# Teensylu-1_2.net
KiCad netlist of a schematic drawn in EAGLE
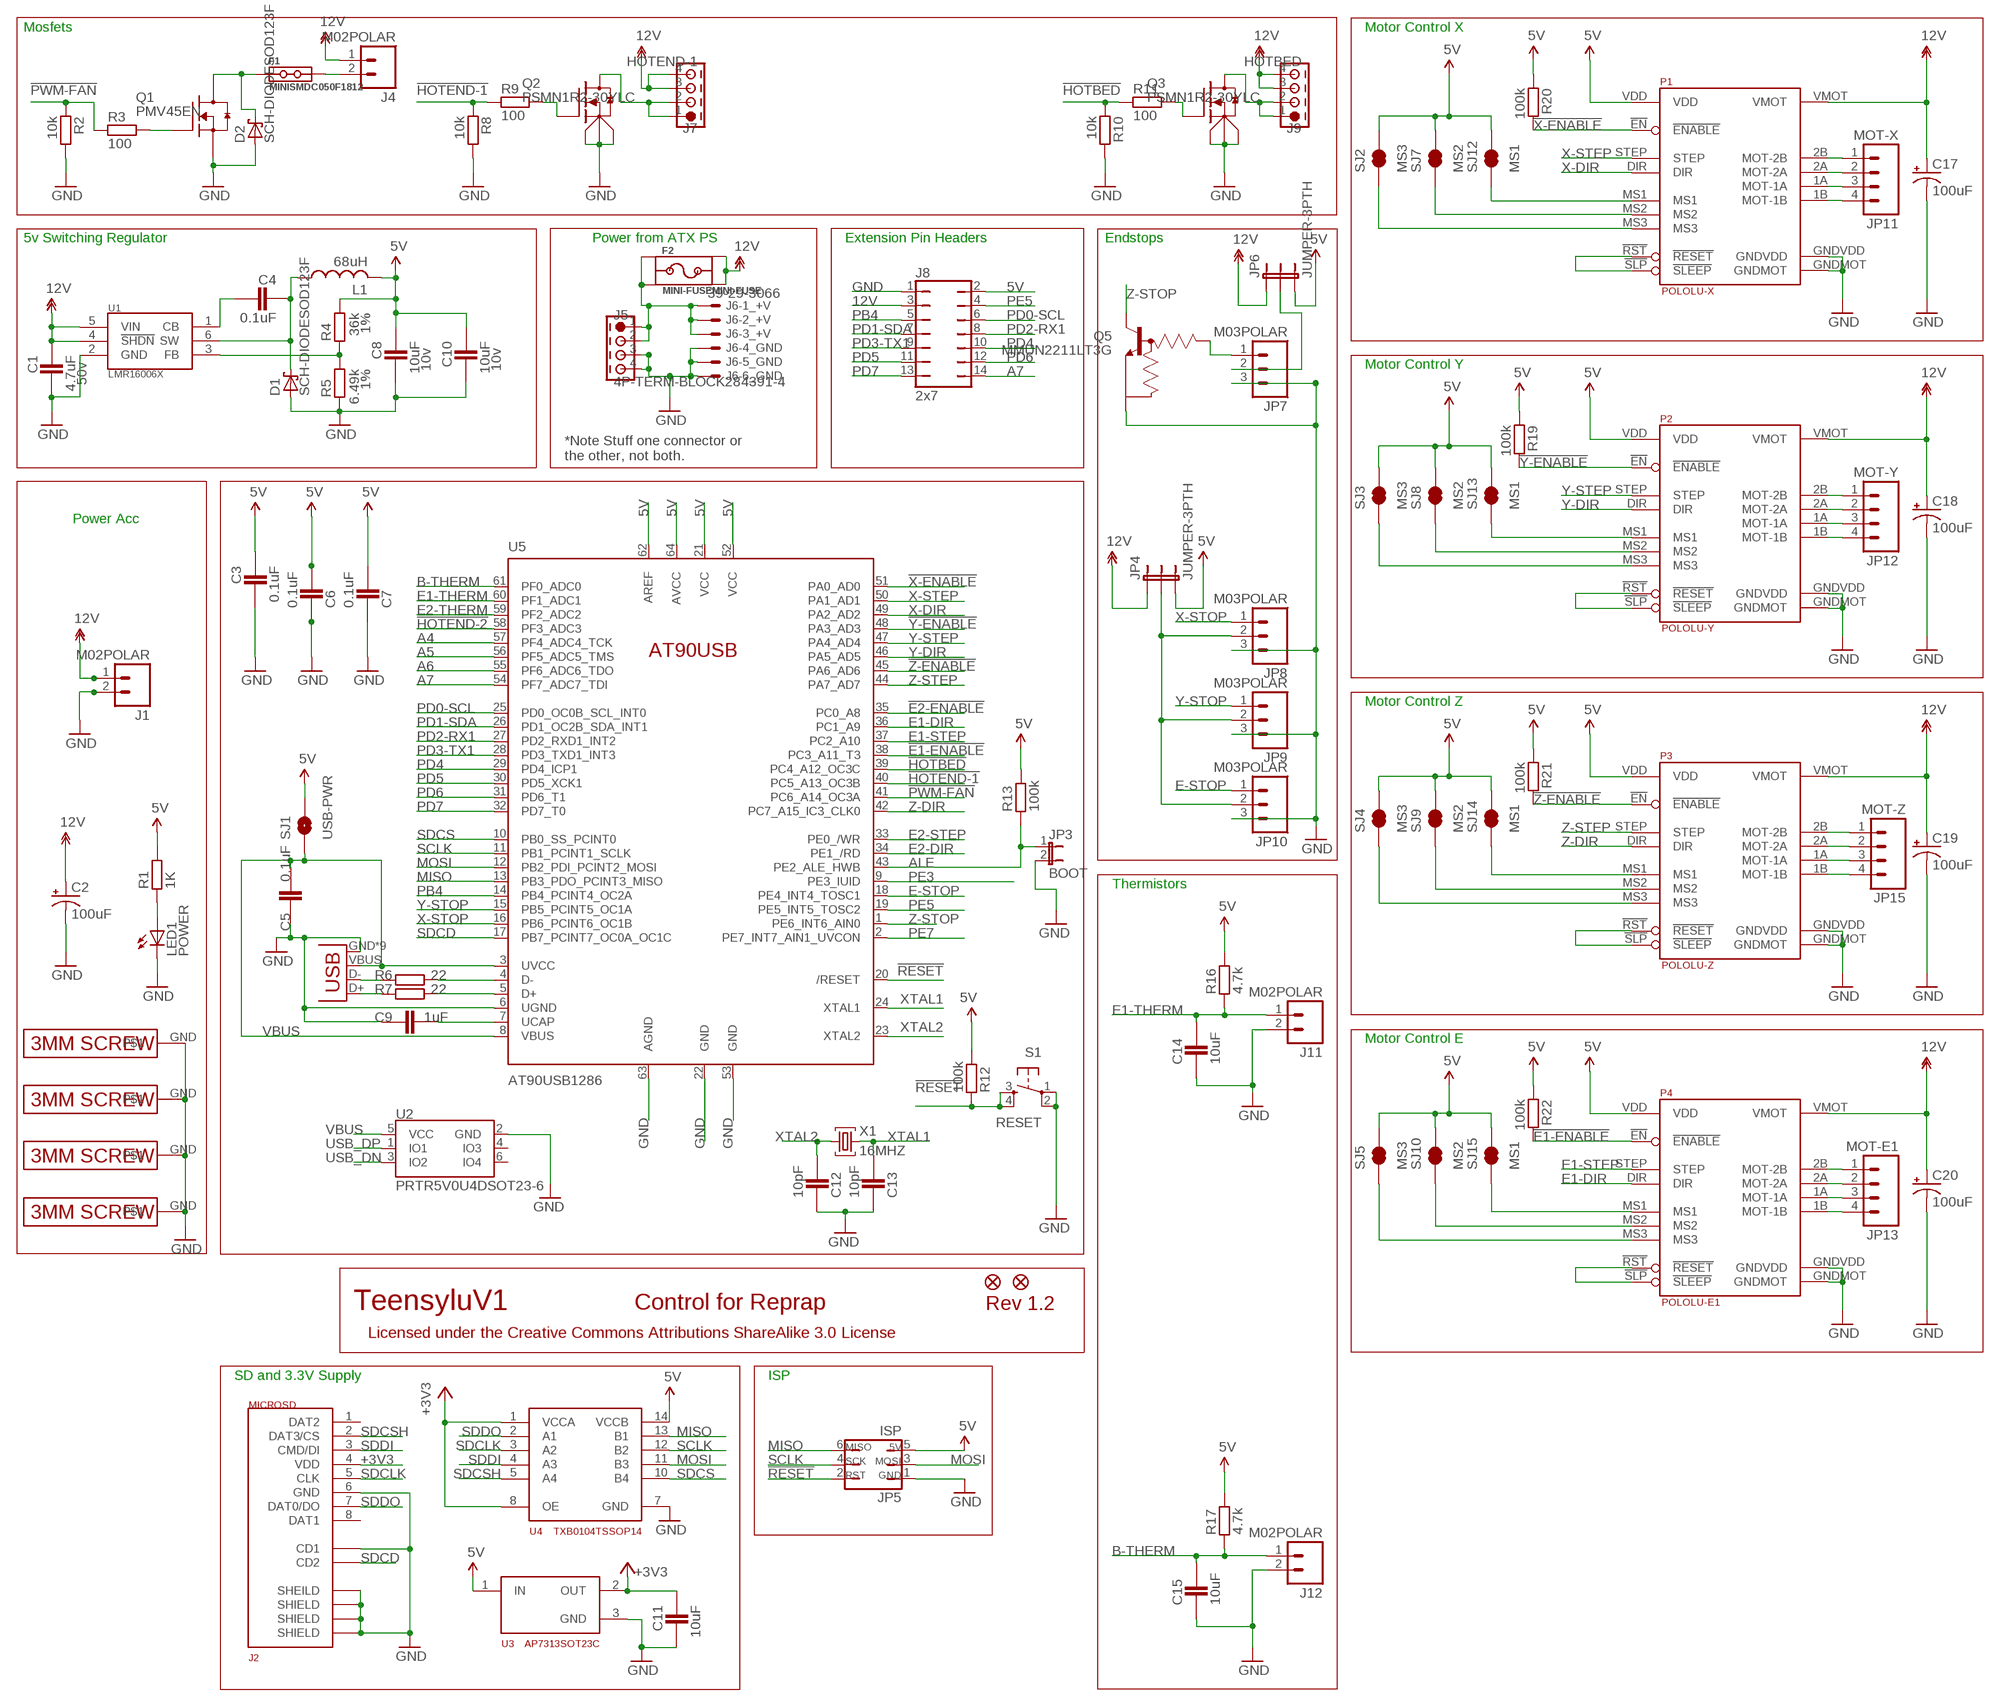
[diagram p0: schematic, sheet 1]

(export (version "E")
  (design (tool "Eeschema 10.0.6"))
  (components
    (comp (ref "C1")
      (value "4.7uF")
      (footprint "eagle-import:CAPC3215X168N")
      (fields
        (field (name "MANUFACTURER") "Yaiyo Yuden")
        (field (name "MANUFACTURER_PART_NUMBER") "UMK316AB7475KL-T")
        (field (name "TOLERANCE") "10%")
        (field (name "VDC") "50v")
      )
      (libsource (lib "eagle-import") (part "CAPACITOR_1206"))
    )
    (comp (ref "C2")
      (value "100uF")
      (footprint "eagle-import:PANASONIC_D")
      (fields
        (field (name "MANUFACTURER") "Panasonic")
        (field (name "MANUFACTURER_PART_NUMBER") "EEE-FTH101XAP")
        (field (name "TOLERANCE") "20%")
      )
      (libsource (lib "eagle-import") (part "CPOL-USD"))
    )
    (comp (ref "C3")
      (value "0.1uF")
      (footprint "eagle-import:CAPC1608X92N")
      (fields
        (field (name "MANUFACTURER") "Murata")
        (field (name "MANUFACTURER_PART_NUMBER") "GRM188R71C104KA01D")
        (field (name "TOLERANCE") "10%")
      )
      (libsource (lib "eagle-import") (part "CAPACITOR_0603"))
    )
    (comp (ref "C4")
      (value "0.1uF")
      (footprint "eagle-import:CAPC1608X92N")
      (fields
        (field (name "MANUFACTURER") "Samsung")
        (field (name "MANUFACTURER_PART_NUMBER") "CL10B104KB8NNNC")
        (field (name "TOLERANCE") "10%")
      )
      (libsource (lib "eagle-import") (part "CAPACITOR_0603"))
    )
    (comp (ref "C5")
      (value "0.1uF")
      (footprint "eagle-import:CAPC1608X92N")
      (fields
        (field (name "MANUFACTURER") "Murata")
        (field (name "MANUFACTURER_PART_NUMBER") "GRM188R71C104KA01D")
        (field (name "TOLERANCE") "10%")
      )
      (libsource (lib "eagle-import") (part "CAPACITOR_0603"))
    )
    (comp (ref "C6")
      (value "0.1uF")
      (footprint "eagle-import:CAPC1608X92N")
      (fields
        (field (name "MANUFACTURER") "Murata")
        (field (name "MANUFACTURER_PART_NUMBER") "GRM188R71C104KA01D")
        (field (name "TOLERANCE") "10%")
      )
      (libsource (lib "eagle-import") (part "CAPACITOR_0603"))
    )
    (comp (ref "C7")
      (value "0.1uF")
      (footprint "eagle-import:CAPC1608X92N")
      (fields
        (field (name "MANUFACTURER") "Murata")
        (field (name "MANUFACTURER_PART_NUMBER") "GRM188R71C104KA01D")
        (field (name "TOLERANCE") "10%")
      )
      (libsource (lib "eagle-import") (part "CAPACITOR_0603"))
    )
    (comp (ref "C8")
      (value "10uF")
      (footprint "eagle-import:CAPC2012X145AN")
      (fields
        (field (name "MANUFACTURER") "Murata")
        (field (name "MANUFACTURER_PART_NUMBER") "GRM21BR71A106KE51L")
        (field (name "TOLERANCE") "10%")
        (field (name "VDC") "10v")
      )
      (libsource (lib "eagle-import") (part "CAPACITOR_0805"))
    )
    (comp (ref "C9")
      (value "1uF")
      (footprint "eagle-import:CAPC1608X92N")
      (fields
        (field (name "MANUFACTURER") "Samsung")
        (field (name "MANUFACTURER_PART_NUMBER") "CL10A105MO8NNNC")
        (field (name "TOLERANCE") "20%")
      )
      (libsource (lib "eagle-import") (part "CAPACITOR_0603"))
    )
    (comp (ref "C10")
      (value "10uF")
      (footprint "eagle-import:CAPC2012X145AN")
      (fields
        (field (name "MANUFACTURER") "Murata")
        (field (name "MANUFACTURER_PART_NUMBER") "GRM21BR71A106KE51L")
        (field (name "TOLERANCE") "10%")
        (field (name "VDC") "10v")
      )
      (libsource (lib "eagle-import") (part "CAPACITOR_0805"))
    )
    (comp (ref "C11")
      (value "10uF")
      (footprint "eagle-import:CAPC1608X92N")
      (fields
        (field (name "MANUFACTURER") "Murata")
        (field (name "MANUFACTURER_PART_NUMBER") "GRM188R61C106MA73D")
        (field (name "TOLERANCE") "20%")
      )
      (libsource (lib "eagle-import") (part "CAPACITOR_0603"))
    )
    (comp (ref "C12")
      (value "10pF")
      (footprint "eagle-import:CAPC1608X92N")
      (fields
        (field (name "MANUFACTURER") "Samsung")
        (field (name "MANUFACTURER_PART_NUMBER") "CL10C100JB8NCNC")
        (field (name "TOLERANCE") "5%")
      )
      (libsource (lib "eagle-import") (part "CAPACITOR_0603"))
    )
    (comp (ref "C13")
      (value "10pF")
      (footprint "eagle-import:CAPC1608X92N")
      (fields
        (field (name "MANUFACTURER") "Samsung")
        (field (name "MANUFACTURER_PART_NUMBER") "CL10C100JB8NCNC")
        (field (name "TOLERANCE") "5%")
      )
      (libsource (lib "eagle-import") (part "CAPACITOR_0603"))
    )
    (comp (ref "C14")
      (value "10uF")
      (footprint "eagle-import:CAPC1608X92N")
      (fields
        (field (name "MANUFACTURER") "Murata")
        (field (name "MANUFACTURER_PART_NUMBER") "GRM188R61C106MA73D")
        (field (name "TOLERANCE") "20%")
      )
      (libsource (lib "eagle-import") (part "CAPACITOR_0603"))
    )
    (comp (ref "C15")
      (value "10uF")
      (footprint "eagle-import:CAPC1608X92N")
      (fields
        (field (name "MANUFACTURER") "Murata")
        (field (name "MANUFACTURER_PART_NUMBER") "GRM188R61C106MA73D")
        (field (name "TOLERANCE") "20%")
      )
      (libsource (lib "eagle-import") (part "CAPACITOR_0603"))
    )
    (comp (ref "C17")
      (value "100uF")
      (footprint "eagle-import:PANASONIC_D")
      (fields
        (field (name "MANUFACTURER") "Panasonic")
        (field (name "MANUFACTURER_PART_NUMBER") "EEE-FTH101XAP")
        (field (name "TOLERANCE") "20%")
      )
      (libsource (lib "eagle-import") (part "CPOL-USD"))
    )
    (comp (ref "C18")
      (value "100uF")
      (footprint "eagle-import:PANASONIC_D")
      (fields
        (field (name "MANUFACTURER") "Panasonic")
        (field (name "MANUFACTURER_PART_NUMBER") "EEE-FTH101XAP")
        (field (name "TOLERANCE") "20%")
      )
      (libsource (lib "eagle-import") (part "CPOL-USD"))
    )
    (comp (ref "C19")
      (value "100uF")
      (footprint "eagle-import:PANASONIC_D")
      (fields
        (field (name "MANUFACTURER") "Panasonic")
        (field (name "MANUFACTURER_PART_NUMBER") "EEE-FTH101XAP")
        (field (name "TOLERANCE") "20%")
      )
      (libsource (lib "eagle-import") (part "CPOL-USD"))
    )
    (comp (ref "C20")
      (value "100uF")
      (footprint "eagle-import:PANASONIC_D")
      (fields
        (field (name "MANUFACTURER") "Panasonic")
        (field (name "MANUFACTURER_PART_NUMBER") "EEE-FTH101XAP")
        (field (name "TOLERANCE") "20%")
      )
      (libsource (lib "eagle-import") (part "CPOL-USD"))
    )
    (comp (ref "D1")
      (value "SCH-DIODESOD123F")
      (footprint "eagle-import:SOD123F")
      (fields
        (field (name "MANUFACTURER") "NXP Semiconductors")
        (field (name "MANUFACTURER_PART_NUMBER") "PMEG4010CEH,115")
        (field (name "CURRENT") "1A")
        (field (name "MANUFACTURER_1") "NXP Semiconductors")
        (field (name "MANUFACTURER_PART_NUMBER_1") "PMEG4010CEH,115")
        (field (name "REVERSE_VOLTAGE") "40V")
      )
      (libsource (lib "eagle-import") (part "SCH-DIODESOD123F"))
    )
    (comp (ref "D2")
      (value "SCH-DIODESOD123F")
      (footprint "eagle-import:SOD123F")
      (fields
        (field (name "MANUFACTURER") "NXP Semiconductors")
        (field (name "MANUFACTURER_PART_NUMBER") "PMEG4010CEH,115")
        (field (name "CURRENT") "1A")
        (field (name "MANUFACTURER_1") "NXP Semiconductors")
      )
      (libsource (lib "eagle-import") (part "SCH-DIODESOD123F"))
    )
    (comp (ref "F1")
      (value "MINISMDC050F1812")
      (footprint "eagle-import:MINISMDC")
      (fields
        (field (name "MANUFACTURER") "TE Connectivity")
        (field (name "MANUFACTURER_PART_NUMBER") "MINISMDC050F-2")
      )
      (libsource (lib "eagle-import") (part "MINISMDC050F1812"))
    )
    (comp (ref "F2")
      (value "MINI-FUSEMINI-FUSE")
      (footprint "eagle-import:MINI_FUSE")
      (fields (field (name "MANUFACTURER") "Keystone") (field (name "MANUFACTURER_PART_NUMBER") "3568"))
      (libsource (lib "eagle-import") (part "MINI-FUSEMINI-FUSE"))
    )
    (comp (ref "J1")
      (value "M02POLAR")
      (footprint "eagle-import:MOLEX-1X2")
      (description "CONN HEADER 2POS .100 VERT TIN")
      (fields (field (name "MANUFACTURER") "Molex") (field (name "MANUFACTURER_PART_NUMBER") "0022272021"))
      (libsource (lib "eagle-import") (part "M02POLAR"))
    )
    (comp (ref "J2")
      (value "MICROSD")
      (footprint "eagle-import:AMPHENOL-MICROSD")
      (description "CONN MICRO SD CARD PUSH-PULL R/A")
      (fields
        (field (name "MANUFACTURER") "Amphenol")
        (field (name "MANUFACTURER_PART_NUMBER") "114-00841-68")
      )
      (libsource (lib "eagle-import") (part "MICROSD"))
    )
    (comp (ref "J3")
      (value "USB-MICRO-PTH")
      (footprint "eagle-import:USB-MICROB-PTH")
      (fields (field (name "MANUFACTURER") "FCI") (field (name "MANUFACTURER_PART_NUMBER") "10118194-0001LF"))
      (libsource (lib "eagle-import") (part "USB-MICRO-PTH"))
    )
    (comp (ref "J4")
      (value "M02POLAR")
      (footprint "eagle-import:MOLEX-1X2")
      (description "CONN HEADER 2POS .100 VERT TIN")
      (fields (field (name "MANUFACTURER") "Molex") (field (name "MANUFACTURER_PART_NUMBER") "0022272021"))
      (libsource (lib "eagle-import") (part "M02POLAR"))
    )
    (comp (ref "J5")
      (value "4P-TERM-BLOCK284391-4")
      (footprint "eagle-import:284391-4")
      (fields
        (field (name "MANUFACTURER") "TE Connectivity")
        (field (name "MANUFACTURER_PART_NUMBER") "284391-4")
      )
      (libsource (lib "eagle-import") (part "4P-TERM-BLOCK284391-4"))
    )
    (comp (ref "J6")
      (value "39-29-3066")
      (footprint "eagle-import:39-29-3066")
      (fields (field (name "MANUFACTURER") "Molex") (field (name "MANUFACTURER_PART_NUMBER") "0039293066"))
      (libsource (lib "eagle-import") (part "39-29-3066"))
    )
    (comp (ref "J7")
      (value "HOTEND-1")
      (footprint "eagle-import:284391-4")
      (fields
        (field (name "MANUFACTURER") "TE Connectivity")
        (field (name "MANUFACTURER_PART_NUMBER") "284391-4")
      )
      (libsource (lib "eagle-import") (part "4P-TERM-BLOCK284391-4"))
    )
    (comp (ref "J8")
      (value "2x7")
      (footprint "eagle-import:JP7Q")
      (description "DIL VERTICAL PC TAIL PIN HEADER")
      (fields (field (name "MANUFACTURER") "Harwin") (field (name "MANUFACTURER_PART_NUMBER") "M20-9980746"))
      (libsource (lib "eagle-import") (part "JP7Q"))
    )
    (comp (ref "J9")
      (value "HOTBED")
      (footprint "eagle-import:284391-4")
      (fields
        (field (name "MANUFACTURER") "TE Connectivity")
        (field (name "MANUFACTURER_PART_NUMBER") "284391-4")
      )
      (libsource (lib "eagle-import") (part "4P-TERM-BLOCK284391-4"))
    )
    (comp (ref "J11")
      (value "M02POLAR")
      (footprint "eagle-import:MOLEX-1X2")
      (description "CONN HEADER 2POS .100 VERT TIN")
      (fields (field (name "MANUFACTURER") "Molex") (field (name "MANUFACTURER_PART_NUMBER") "0022272021"))
      (libsource (lib "eagle-import") (part "M02POLAR"))
    )
    (comp (ref "J12")
      (value "M02POLAR")
      (footprint "eagle-import:MOLEX-1X2")
      (description "CONN HEADER 2POS .100 VERT TIN")
      (fields (field (name "MANUFACTURER") "Molex") (field (name "MANUFACTURER_PART_NUMBER") "0022272021"))
      (libsource (lib "eagle-import") (part "M02POLAR"))
    )
    (comp (ref "JP1")
      (value "FIDUCIAL1X2.5")
      (footprint "eagle-import:FIDUCIAL-1X2.5")
      (libsource (lib "eagle-import") (part "FIDUCIAL1X2.5"))
    )
    (comp (ref "JP2")
      (value "FIDUCIAL1X2.5")
      (footprint "eagle-import:FIDUCIAL-1X2.5")
      (libsource (lib "eagle-import") (part "FIDUCIAL1X2.5"))
    )
    (comp (ref "JP3")
      (value "BOOT")
      (footprint "eagle-import:1X02")
      (description "SIL VERTICAL PC TAIL PIN HEADER")
      (fields (field (name "MANUFACTURER") "Harwin") (field (name "MANUFACTURER_PART_NUMBER") "M20-9990246"))
      (libsource (lib "eagle-import") (part "JUMPER-2PTH"))
    )
    (comp (ref "JP4")
      (value "JUMPER-3PTH")
      (footprint "eagle-import:1X03")
      (libsource (lib "eagle-import") (part "JUMPER-3PTH"))
    )
    (comp (ref "JP5")
      (value "ISP")
      (footprint "eagle-import:ISP")
      (libsource (lib "eagle-import") (part "PROGHEADER"))
    )
    (comp (ref "JP6")
      (value "JUMPER-3PTH")
      (footprint "eagle-import:1X03")
      (libsource (lib "eagle-import") (part "JUMPER-3PTH"))
    )
    (comp (ref "JP7")
      (value "M03POLAR")
      (footprint "eagle-import:MOLEX-1X3")
      (description "CONN HEADER 3POS .100 VERT TIN")
      (fields (field (name "MANUFACTURER") "Molex") (field (name "MANUFACTURER_PART_NUMBER") "0022272031"))
      (libsource (lib "eagle-import") (part "M03POLAR"))
    )
    (comp (ref "JP8")
      (value "M03POLAR")
      (footprint "eagle-import:MOLEX-1X3")
      (description "CONN HEADER 3POS .100 VERT TIN")
      (fields (field (name "MANUFACTURER") "Molex") (field (name "MANUFACTURER_PART_NUMBER") "0022272031"))
      (libsource (lib "eagle-import") (part "M03POLAR"))
    )
    (comp (ref "JP9")
      (value "M03POLAR")
      (footprint "eagle-import:MOLEX-1X3")
      (description "CONN HEADER 3POS .100 VERT TIN")
      (fields (field (name "MANUFACTURER") "Molex") (field (name "MANUFACTURER_PART_NUMBER") "0022272031"))
      (libsource (lib "eagle-import") (part "M03POLAR"))
    )
    (comp (ref "JP10")
      (value "M03POLAR")
      (footprint "eagle-import:MOLEX-1X3")
      (description "CONN HEADER 3POS .100 VERT TIN")
      (fields (field (name "MANUFACTURER") "Molex") (field (name "MANUFACTURER_PART_NUMBER") "0022272031"))
      (libsource (lib "eagle-import") (part "M03POLAR"))
    )
    (comp (ref "JP11")
      (value "MOT-X")
      (footprint "eagle-import:MOLEX-1X4")
      (fields (field (name "MANUFACTURER") "Molex") (field (name "MANUFACTURER_PART_NUMBER") "0022272041"))
      (libsource (lib "eagle-import") (part "M04POLAR"))
    )
    (comp (ref "JP12")
      (value "MOT-Y")
      (footprint "eagle-import:MOLEX-1X4")
      (fields (field (name "MANUFACTURER") "Molex") (field (name "MANUFACTURER_PART_NUMBER") "0022272041"))
      (libsource (lib "eagle-import") (part "M04POLAR"))
    )
    (comp (ref "JP13")
      (value "MOT-E1")
      (footprint "eagle-import:MOLEX-1X4")
      (fields (field (name "MANUFACTURER") "Molex") (field (name "MANUFACTURER_PART_NUMBER") "0022272041"))
      (libsource (lib "eagle-import") (part "M04POLAR"))
    )
    (comp (ref "JP15")
      (value "MOT-Z")
      (footprint "eagle-import:MOLEX-1X4")
      (fields (field (name "MANUFACTURER") "Molex") (field (name "MANUFACTURER_PART_NUMBER") "0022272041"))
      (libsource (lib "eagle-import") (part "M04POLAR"))
    )
    (comp (ref "L1")
      (value "68uH")
      (footprint "eagle-import:SRN6045")
      (fields
        (field (name "MANUFACTURER") "Bourns")
        (field (name "MANUFACTURER_PART_NUMBER") "SRN6045-680M")
        (field (name "MANUFACTURER_1") "Bourns")
        (field (name "MANUFACTURER_PART_NUMBER_1") "SRN6045-680M")
      )
      (libsource (lib "eagle-import") (part "INDUCTORSRN6045"))
    )
    (comp (ref "LED1")
      (value "POWER")
      (footprint "eagle-import:CHIPLED_0805")
      (fields
        (field (name "MANUFACTURER") "Kingbright")
        (field (name "MANUFACTURER_PART_NUMBER") "APT2012SGC")
      )
      (libsource (lib "eagle-import") (part "LEDCHIPLED_0805"))
    )
    (comp (ref "P1")
      (value "POLOLU-X")
      (footprint "eagle-import:POLOLU-STEPPER-PTH")
      (libsource (lib "eagle-import") (part "POLOLU-ALLEGRO"))
    )
    (comp (ref "P2")
      (value "POLOLU-Y")
      (footprint "eagle-import:POLOLU-STEPPER-PTH")
      (libsource (lib "eagle-import") (part "POLOLU-ALLEGRO"))
    )
    (comp (ref "P3")
      (value "POLOLU-Z")
      (footprint "eagle-import:POLOLU-STEPPER-PTH")
      (libsource (lib "eagle-import") (part "POLOLU-ALLEGRO"))
    )
    (comp (ref "P4")
      (value "POLOLU-E1")
      (footprint "eagle-import:POLOLU-STEPPER-PTH")
      (libsource (lib "eagle-import") (part "POLOLU-ALLEGRO"))
    )
    (comp (ref "Q1")
      (value "PMV45EN")
      (footprint "eagle-import:SOT23C")
      (fields
        (field (name "MANUFACTURER") "International Rectifier")
        (field (name "MANUFACTURER_PART_NUMBER") "IRLML2060TRPBF")
        (field (name "VOLTAGE") "60V")
      )
      (libsource (lib "eagle-import") (part "MOSFET-NCH_SOT-23"))
    )
    (comp (ref "Q2")
      (value "PSMN1R2-30YLC")
      (footprint "eagle-import:LFPACK-POWERPAK-SO8")
      (fields
        (field (name "MANUFACTURER") "NXP Semiconductors")
        (field (name "MANUFACTURER_PART_NUMBER") "PSMN1R2-30YLC,115")
        (field (name "VOLTAGE") "30V")
      )
      (libsource (lib "eagle-import") (part "PSMN1R2-30YLCPOWERPACK-S08"))
    )
    (comp (ref "Q3")
      (value "PSMN1R2-30YLC")
      (footprint "eagle-import:LFPACK-POWERPAK-SO8")
      (fields
        (field (name "MANUFACTURER") "NXP Semiconductors")
        (field (name "MANUFACTURER_PART_NUMBER") "PSMN1R2-30YLC,115")
        (field (name "VOLTAGE") "30V")
      )
      (libsource (lib "eagle-import") (part "PSMN1R2-30YLCPOWERPACK-S08"))
    )
    (comp (ref "Q5")
      (value "MMUN2211LT3G")
      (footprint "eagle-import:SOT23C")
      (description "TRANS PREBIAS NPN 246MW SOT23-3")
      (fields (field (name "MANUFACTURER") "ON Semiconductor"))
      (libsource (lib "eagle-import") (part "TRANSISTOR_NPN_BIASSOT23C"))
    )
    (comp (ref "R1")
      (value "1K")
      (footprint "eagle-import:RESC1608X55N")
      (libsource (lib "eagle-import") (part "RESISTOR_0603"))
    )
    (comp (ref "R2")
      (value "10k")
      (footprint "eagle-import:RESC1608X55N")
      (libsource (lib "eagle-import") (part "RESISTOR_0603"))
    )
    (comp (ref "R3")
      (value "100")
      (footprint "eagle-import:RESC1608X55N")
      (libsource (lib "eagle-import") (part "RESISTOR_0603"))
    )
    (comp (ref "R4")
      (value "36k")
      (footprint "eagle-import:RESC1608X55N")
      (fields (field (name "TOLERANCE") "1%"))
      (libsource (lib "eagle-import") (part "RESISTOR_0603"))
    )
    (comp (ref "R5")
      (value "6.49k")
      (footprint "eagle-import:RESC1608X55N")
      (fields (field (name "TOLERANCE") "1%"))
      (libsource (lib "eagle-import") (part "RESISTOR_0603"))
    )
    (comp (ref "R6")
      (value "22")
      (footprint "eagle-import:RESC1608X55N")
      (libsource (lib "eagle-import") (part "RESISTOR_0603"))
    )
    (comp (ref "R7")
      (value "22")
      (footprint "eagle-import:RESC1608X55N")
      (libsource (lib "eagle-import") (part "RESISTOR_0603"))
    )
    (comp (ref "R8")
      (value "10k")
      (footprint "eagle-import:RESC1608X55N")
      (libsource (lib "eagle-import") (part "RESISTOR_0603"))
    )
    (comp (ref "R9")
      (value "100")
      (footprint "eagle-import:RESC1608X55N")
      (libsource (lib "eagle-import") (part "RESISTOR_0603"))
    )
    (comp (ref "R10")
      (value "10k")
      (footprint "eagle-import:RESC1608X55N")
      (libsource (lib "eagle-import") (part "RESISTOR_0603"))
    )
    (comp (ref "R11")
      (value "100")
      (footprint "eagle-import:RESC1608X55N")
      (libsource (lib "eagle-import") (part "RESISTOR_0603"))
    )
    (comp (ref "R12")
      (value "100k")
      (footprint "eagle-import:RESC1608X55N")
      (libsource (lib "eagle-import") (part "RESISTOR_0603"))
    )
    (comp (ref "R13")
      (value "100k")
      (footprint "eagle-import:RESC1608X55N")
      (libsource (lib "eagle-import") (part "RESISTOR_0603"))
    )
    (comp (ref "R16")
      (value "4.7k")
      (footprint "eagle-import:RESC1608X55N")
      (libsource (lib "eagle-import") (part "RESISTOR_0603"))
    )
    (comp (ref "R17")
      (value "4.7k")
      (footprint "eagle-import:RESC1608X55N")
      (libsource (lib "eagle-import") (part "RESISTOR_0603"))
    )
    (comp (ref "R19")
      (value "100k")
      (footprint "eagle-import:RESC1608X55N")
      (libsource (lib "eagle-import") (part "RESISTOR_0603"))
    )
    (comp (ref "R20")
      (value "100k")
      (footprint "eagle-import:RESC1608X55N")
      (libsource (lib "eagle-import") (part "RESISTOR_0603"))
    )
    (comp (ref "R21")
      (value "100k")
      (footprint "eagle-import:RESC1608X55N")
      (libsource (lib "eagle-import") (part "RESISTOR_0603"))
    )
    (comp (ref "R22")
      (value "100k")
      (footprint "eagle-import:RESC1608X55N")
      (libsource (lib "eagle-import") (part "RESISTOR_0603"))
    )
    (comp (ref "S1")
      (value "RESET")
      (footprint "eagle-import:TACTILE_SWITCH_SMD")
      (fields (field (name "MANUFACTURER") "Bourns") (field (name "MANUFACTURER_PART_NUMBER") "7914J-1-000E"))
      (libsource (lib "eagle-import") (part "TAC_SWITCHSMD"))
    )
    (comp (ref "SCREW1")
      (value "3MM-SCREW")
      (footprint "eagle-import:PLATEDSCREW")
      (libsource (lib "eagle-import") (part "3MM-SCREW"))
    )
    (comp (ref "SCREW2")
      (value "3MM-SCREW")
      (footprint "eagle-import:PLATEDSCREW")
      (libsource (lib "eagle-import") (part "3MM-SCREW"))
    )
    (comp (ref "SCREW3")
      (value "3MM-SCREW")
      (footprint "eagle-import:PLATEDSCREW")
      (libsource (lib "eagle-import") (part "3MM-SCREW"))
    )
    (comp (ref "SCREW4")
      (value "3MM-SCREW")
      (footprint "eagle-import:PLATEDSCREW")
      (libsource (lib "eagle-import") (part "3MM-SCREW"))
    )
    (comp (ref "SJ1")
      (value "USB-PWR")
      (footprint "eagle-import:SJ_2S-NO")
      (libsource (lib "eagle-import") (part "SOLDERJUMPERNO"))
    )
    (comp (ref "SJ2")
      (value "MS3")
      (footprint "eagle-import:SJ_2S-TRACE")
      (libsource (lib "eagle-import") (part "SOLDERJUMPER-NCSJ-TRACE"))
    )
    (comp (ref "SJ3")
      (value "MS3")
      (footprint "eagle-import:SJ_2S-TRACE")
      (libsource (lib "eagle-import") (part "SOLDERJUMPER-NCSJ-TRACE"))
    )
    (comp (ref "SJ4")
      (value "MS3")
      (footprint "eagle-import:SJ_2S-TRACE")
      (libsource (lib "eagle-import") (part "SOLDERJUMPER-NCSJ-TRACE"))
    )
    (comp (ref "SJ5")
      (value "MS3")
      (footprint "eagle-import:SJ_2S-TRACE")
      (libsource (lib "eagle-import") (part "SOLDERJUMPER-NCSJ-TRACE"))
    )
    (comp (ref "SJ7")
      (value "MS2")
      (footprint "eagle-import:SJ_2S-TRACE")
      (libsource (lib "eagle-import") (part "SOLDERJUMPER-NCSJ-TRACE"))
    )
    (comp (ref "SJ8")
      (value "MS2")
      (footprint "eagle-import:SJ_2S-TRACE")
      (libsource (lib "eagle-import") (part "SOLDERJUMPER-NCSJ-TRACE"))
    )
    (comp (ref "SJ9")
      (value "MS2")
      (footprint "eagle-import:SJ_2S-TRACE")
      (libsource (lib "eagle-import") (part "SOLDERJUMPER-NCSJ-TRACE"))
    )
    (comp (ref "SJ10")
      (value "MS2")
      (footprint "eagle-import:SJ_2S-TRACE")
      (libsource (lib "eagle-import") (part "SOLDERJUMPER-NCSJ-TRACE"))
    )
    (comp (ref "SJ12")
      (value "MS1")
      (footprint "eagle-import:SJ_2S-TRACE")
      (libsource (lib "eagle-import") (part "SOLDERJUMPER-NCSJ-TRACE"))
    )
    (comp (ref "SJ13")
      (value "MS1")
      (footprint "eagle-import:SJ_2S-TRACE")
      (libsource (lib "eagle-import") (part "SOLDERJUMPER-NCSJ-TRACE"))
    )
    (comp (ref "SJ14")
      (value "MS1")
      (footprint "eagle-import:SJ_2S-TRACE")
      (libsource (lib "eagle-import") (part "SOLDERJUMPER-NCSJ-TRACE"))
    )
    (comp (ref "SJ15")
      (value "MS1")
      (footprint "eagle-import:SJ_2S-TRACE")
      (libsource (lib "eagle-import") (part "SOLDERJUMPER-NCSJ-TRACE"))
    )
    (comp (ref "U1")
      (value "LMR16006X")
      (footprint "eagle-import:TSOT6")
      (fields
        (field (name "MANUFACTURER") "Texas Instruments")
        (field (name "MANUFACTURER_PART_NUMBER") "LMR16006XDDCT")
      )
      (libsource (lib "eagle-import") (part "LMR16006X"))
    )
    (comp (ref "U2")
      (value "PRTR5V0U4DSOT23-6")
      (footprint "eagle-import:SOT23-6")
      (fields
        (field (name "MANUFACTURER") "NXP Semiconductors")
        (field (name "MANUFACTURER_PART_NUMBER") "PRTR5V0U4D,125")
      )
      (libsource (lib "eagle-import") (part "PRTR5V0U4DSOT23-6"))
    )
    (comp (ref "U3")
      (value "AP7313SOT23C")
      (footprint "eagle-import:SOT23C")
      (description "IC REG LDO 3.3V 0.15A SOT23-3")
      (fields
        (field (name "MANUFACTURER") "Diodes Incorporated")
        (field (name "MANUFACTURER_PART_NUMBER") "AP7313-33SAG-7")
      )
      (libsource (lib "eagle-import") (part "AP7313SOT23C"))
    )
    (comp (ref "U4")
      (value "TXB0104TSSOP14")
      (footprint "eagle-import:TSSOP14")
      (description "IC VOLT-LEVEL TRANSLATOR 14TSSOP")
      (fields
        (field (name "MANUFACTURER") "Texas Instruments")
        (field (name "MANUFACTURER_PART_NUMBER") "TXB0104PWR")
      )
      (libsource (lib "eagle-import") (part "TXB0104TSSOP14"))
    )
    (comp (ref "U5")
      (value "AT90USB1286")
      (footprint "eagle-import:TQFP64-2")
      (fields (field (name "MANUFACTURER") "Atmel"))
      (libsource (lib "eagle-import") (part "AT90USB"))
    )
    (comp (ref "X1")
      (value "16MHZ")
      (footprint "eagle-import:NDK-XTAL")
      (fields
        (field (name "MANUFACTURER") "NDK")
        (field (name "MANUFACTURER_PART_NUMBER") "NX5032GA-16.000000MHZ-LN-CD-1")
      )
      (libsource (lib "eagle-import") (part "XTAL"))
    )
  )
  (nets
    (net (code "1") (name "+3V3") (class "Default")
      (node (ref "C11") (pin "1") (pinfunction "1_1") (pintype "passive"))
      (node (ref "J2") (pin "4") (pinfunction "VDD_4") (pintype "power_in"))
      (node (ref "U3") (pin "2") (pinfunction "OUT_2") (pintype "power_in"))
      (node (ref "U4") (pin "1") (pinfunction "VCCA_1") (pintype "power_in"))
      (node (ref "U4") (pin "8") (pinfunction "OE_8") (pintype "input"))
    )
    (net (code "2") (name "/A4") (class "Default")
      (node (ref "U5") (pin "57") (pinfunction "PF4_ADC4_TCK_57") (pintype "bidirectional"))
    )
    (net (code "3") (name "/A5") (class "Default")
      (node (ref "U5") (pin "56") (pinfunction "PF5_ADC5_TMS_56") (pintype "bidirectional"))
    )
    (net (code "4") (name "/A6") (class "Default")
      (node (ref "U5") (pin "55") (pinfunction "PF6_ADC6_TDO_55") (pintype "bidirectional"))
    )
    (net (code "5") (name "/A7") (class "Default")
      (node (ref "J8") (pin "14") (pinfunction "14_14") (pintype "passive"))
      (node (ref "U5") (pin "54") (pinfunction "PF7_ADC7_TDI_54") (pintype "bidirectional"))
    )
    (net (code "6") (name "/ALE") (class "Default")
      (node (ref "JP3") (pin "1") (pinfunction "1_1") (pintype "passive"))
      (node (ref "R13") (pin "1") (pinfunction "1_1") (pintype "passive"))
      (node (ref "U5") (pin "43") (pinfunction "PE2_ALE_HWB_43") (pintype "bidirectional"))
    )
    (net (code "7") (name "/B-THERM") (class "Default")
      (node (ref "C15") (pin "2") (pinfunction "2_2") (pintype "passive"))
      (node (ref "J12") (pin "1") (pinfunction "1_1") (pintype "passive"))
      (node (ref "R17") (pin "1") (pinfunction "1_1") (pintype "passive"))
      (node (ref "U5") (pin "61") (pinfunction "PF0_ADC0_61") (pintype "bidirectional"))
    )
    (net (code "8") (name "/E-STOP") (class "Default")
      (node (ref "JP10") (pin "1") (pinfunction "1_1") (pintype "passive"))
      (node (ref "U5") (pin "18") (pinfunction "PE4_INT4_TOSC1_18") (pintype "bidirectional"))
    )
    (net (code "9") (name "/E1-DIR") (class "Default")
      (node (ref "P4") (pin "DIR") (pinfunction "DIR_DIR") (pintype "bidirectional"))
      (node (ref "U5") (pin "36") (pinfunction "PC1_A9_36") (pintype "bidirectional"))
    )
    (net (code "10") (name "/E1-STEP") (class "Default")
      (node (ref "P4") (pin "STEP") (pinfunction "STEP_STEP") (pintype "bidirectional"))
      (node (ref "U5") (pin "37") (pinfunction "PC2_A10_37") (pintype "bidirectional"))
    )
    (net (code "11") (name "/E1-THERM") (class "Default")
      (node (ref "C14") (pin "2") (pinfunction "2_2") (pintype "passive"))
      (node (ref "J11") (pin "1") (pinfunction "1_1") (pintype "passive"))
      (node (ref "R16") (pin "1") (pinfunction "1_1") (pintype "passive"))
      (node (ref "U5") (pin "60") (pinfunction "PF1_ADC1_60") (pintype "bidirectional"))
    )
    (net (code "12") (name "/E2-DIR") (class "Default")
      (node (ref "U5") (pin "34") (pinfunction "PE1_/RD_34") (pintype "bidirectional"))
    )
    (net (code "13") (name "/E2-STEP") (class "Default")
      (node (ref "U5") (pin "33") (pinfunction "PE0_/WR_33") (pintype "bidirectional"))
    )
    (net (code "14") (name "/E2-THERM") (class "Default")
      (node (ref "U5") (pin "59") (pinfunction "PF2_ADC2_59") (pintype "bidirectional"))
    )
    (net (code "15") (name "/MISO") (class "Default")
      (node (ref "JP5") (pin "6") (pinfunction "6_6") (pintype "passive"))
      (node (ref "U4") (pin "13") (pinfunction "B1_13") (pintype "bidirectional"))
      (node (ref "U5") (pin "13") (pinfunction "PB3_PDO_PCINT3_MISO_13") (pintype "bidirectional"))
    )
    (net (code "16") (name "/MOSI") (class "Default")
      (node (ref "JP5") (pin "3") (pinfunction "3_3") (pintype "passive"))
      (node (ref "U4") (pin "11") (pinfunction "B3_11") (pintype "bidirectional"))
      (node (ref "U5") (pin "12") (pinfunction "PB2_PDI_PCINT2_MOSI_12") (pintype "bidirectional"))
    )
    (net (code "17") (name "/PB4") (class "Default")
      (node (ref "J8") (pin "5") (pinfunction "5_5") (pintype "passive"))
      (node (ref "U5") (pin "14") (pinfunction "PB4_PCINT4_OC2A_14") (pintype "bidirectional"))
    )
    (net (code "18") (name "/PD0-SCL") (class "Default")
      (node (ref "J8") (pin "6") (pinfunction "6_6") (pintype "passive"))
      (node (ref "U5") (pin "25") (pinfunction "PD0_OC0B_SCL_INT0_25") (pintype "bidirectional"))
    )
    (net (code "19") (name "/PD1-SDA") (class "Default")
      (node (ref "J8") (pin "7") (pinfunction "7_7") (pintype "passive"))
      (node (ref "U5") (pin "26") (pinfunction "PD1_OC2B_SDA_INT1_26") (pintype "bidirectional"))
    )
    (net (code "20") (name "/PD2-RX1") (class "Default")
      (node (ref "J8") (pin "8") (pinfunction "8_8") (pintype "passive"))
      (node (ref "U5") (pin "27") (pinfunction "PD2_RXD1_INT2_27") (pintype "bidirectional"))
    )
    (net (code "21") (name "/PD3-TX1") (class "Default")
      (node (ref "J8") (pin "9") (pinfunction "9_9") (pintype "passive"))
      (node (ref "U5") (pin "28") (pinfunction "PD3_TXD1_INT3_28") (pintype "bidirectional"))
    )
    (net (code "22") (name "/PD4") (class "Default")
      (node (ref "J8") (pin "10") (pinfunction "10_10") (pintype "passive"))
      (node (ref "U5") (pin "29") (pinfunction "PD4_ICP1_29") (pintype "bidirectional"))
    )
    (net (code "23") (name "/PD5") (class "Default")
      (node (ref "J8") (pin "11") (pinfunction "11_11") (pintype "passive"))
      (node (ref "U5") (pin "30") (pinfunction "PD5_XCK1_30") (pintype "bidirectional"))
    )
    (net (code "24") (name "/PD6") (class "Default")
      (node (ref "J8") (pin "12") (pinfunction "12_12") (pintype "passive"))
      (node (ref "U5") (pin "31") (pinfunction "PD6_T1_31") (pintype "bidirectional"))
    )
    (net (code "25") (name "/PD7") (class "Default")
      (node (ref "J8") (pin "13") (pinfunction "13_13") (pintype "passive"))
      (node (ref "U5") (pin "32") (pinfunction "PD7_T0_32") (pintype "bidirectional"))
    )
    (net (code "26") (name "/PE3") (class "Default")
      (node (ref "U5") (pin "9") (pinfunction "PE3_IUID_9") (pintype "bidirectional"))
    )
    (net (code "27") (name "/PE5") (class "Default")
      (node (ref "J8") (pin "4") (pinfunction "4_4") (pintype "passive"))
      (node (ref "U5") (pin "19") (pinfunction "PE5_INT5_TOSC2_19") (pintype "bidirectional"))
    )
    (net (code "28") (name "/PE7") (class "Default")
      (node (ref "U5") (pin "2") (pinfunction "PE7_INT7_AIN1_UVCON_2") (pintype "bidirectional"))
    )
    (net (code "29") (name "/SCLK") (class "Default")
      (node (ref "JP5") (pin "4") (pinfunction "4_4") (pintype "passive"))
      (node (ref "U4") (pin "12") (pinfunction "B2_12") (pintype "bidirectional"))
      (node (ref "U5") (pin "11") (pinfunction "PB1_PCINT1_SCLK_11") (pintype "bidirectional"))
    )
    (net (code "30") (name "/SDCD") (class "Default")
      (node (ref "J2") (pin "CD2") (pinfunction "CD2_CD2") (pintype "bidirectional"))
      (node (ref "U5") (pin "17") (pinfunction "PB7_PCINT7_OC0A_OC1C_17") (pintype "bidirectional"))
    )
    (net (code "31") (name "/SDCLK") (class "Default")
      (node (ref "J2") (pin "5") (pinfunction "CLK_5") (pintype "input"))
      (node (ref "U4") (pin "3") (pinfunction "A2_3") (pintype "bidirectional"))
    )
    (net (code "32") (name "/SDCS") (class "Default")
      (node (ref "U4") (pin "10") (pinfunction "B4_10") (pintype "bidirectional"))
      (node (ref "U5") (pin "10") (pinfunction "PB0_SS_PCINT0_10") (pintype "bidirectional"))
    )
    (net (code "33") (name "/SDCSH") (class "Default")
      (node (ref "J2") (pin "2") (pinfunction "DAT3/CS_2") (pintype "bidirectional"))
      (node (ref "U4") (pin "5") (pinfunction "A4_5") (pintype "bidirectional"))
    )
    (net (code "34") (name "/SDDI") (class "Default")
      (node (ref "J2") (pin "3") (pinfunction "CMD/DI_3") (pintype "input"))
      (node (ref "U4") (pin "4") (pinfunction "A3_4") (pintype "bidirectional"))
    )
    (net (code "35") (name "/SDDO") (class "Default")
      (node (ref "J2") (pin "7") (pinfunction "DAT0/DO_7") (pintype "bidirectional"))
      (node (ref "U4") (pin "2") (pinfunction "A1_2") (pintype "bidirectional"))
    )
    (net (code "36") (name "/USB_DN") (class "Default")
      (node (ref "J3") (pin "D-") (pinfunction "D-_D-") (pintype "bidirectional"))
      (node (ref "R6") (pin "1") (pinfunction "1_1") (pintype "passive"))
      (node (ref "U2") (pin "3") (pinfunction "IO2_3") (pintype "bidirectional"))
    )
    (net (code "37") (name "/USB_DP") (class "Default")
      (node (ref "J3") (pin "D+") (pinfunction "D+_D+") (pintype "bidirectional"))
      (node (ref "R7") (pin "1") (pinfunction "1_1") (pintype "passive"))
      (node (ref "U2") (pin "1") (pinfunction "IO1_1") (pintype "bidirectional"))
    )
    (net (code "38") (name "/VBUS") (class "Default")
      (node (ref "C5") (pin "2") (pinfunction "2_2") (pintype "passive"))
      (node (ref "J3") (pin "VBUS") (pinfunction "VBUS_VBUS") (pintype "bidirectional"))
      (node (ref "SJ1") (pin "1") (pinfunction "1_1") (pintype "passive"))
      (node (ref "U2") (pin "5") (pinfunction "VCC_5") (pintype "power_in"))
      (node (ref "U5") (pin "3") (pinfunction "UVCC_3") (pintype "power_in"))
      (node (ref "U5") (pin "8") (pinfunction "VBUS_8") (pintype "bidirectional"))
    )
    (net (code "39") (name "/X-DIR") (class "Default")
      (node (ref "P1") (pin "DIR") (pinfunction "DIR_DIR") (pintype "bidirectional"))
      (node (ref "U5") (pin "49") (pinfunction "PA2_AD2_49") (pintype "bidirectional"))
    )
    (net (code "40") (name "/X-STEP") (class "Default")
      (node (ref "P1") (pin "STEP") (pinfunction "STEP_STEP") (pintype "bidirectional"))
      (node (ref "U5") (pin "50") (pinfunction "PA1_AD1_50") (pintype "bidirectional"))
    )
    (net (code "41") (name "/X-STOP") (class "Default")
      (node (ref "JP8") (pin "1") (pinfunction "1_1") (pintype "passive"))
      (node (ref "U5") (pin "16") (pinfunction "PB6_PCINT6_OC1B_16") (pintype "bidirectional"))
    )
    (net (code "42") (name "/XTAL1") (class "Default")
      (node (ref "C13") (pin "2") (pinfunction "2_2") (pintype "passive"))
      (node (ref "U5") (pin "24") (pinfunction "XTAL1_24") (pintype "passive"))
      (node (ref "X1") (pin "P$2") (pinfunction "2_P$2") (pintype "passive"))
    )
    (net (code "43") (name "/XTAL2") (class "Default")
      (node (ref "C12") (pin "2") (pinfunction "2_2") (pintype "passive"))
      (node (ref "U5") (pin "23") (pinfunction "XTAL2_23") (pintype "passive"))
      (node (ref "X1") (pin "P$1") (pinfunction "1_P$1") (pintype "passive"))
    )
    (net (code "44") (name "/Y-DIR") (class "Default")
      (node (ref "P2") (pin "DIR") (pinfunction "DIR_DIR") (pintype "bidirectional"))
      (node (ref "U5") (pin "46") (pinfunction "PA5_AD5_46") (pintype "bidirectional"))
    )
    (net (code "45") (name "/Y-STEP") (class "Default")
      (node (ref "P2") (pin "STEP") (pinfunction "STEP_STEP") (pintype "bidirectional"))
      (node (ref "U5") (pin "47") (pinfunction "PA4_AD4_47") (pintype "bidirectional"))
    )
    (net (code "46") (name "/Y-STOP") (class "Default")
      (node (ref "JP9") (pin "1") (pinfunction "1_1") (pintype "passive"))
      (node (ref "U5") (pin "15") (pinfunction "PB5_PCINT5_OC1A_15") (pintype "bidirectional"))
    )
    (net (code "47") (name "/Z-DIR") (class "Default")
      (node (ref "P3") (pin "DIR") (pinfunction "DIR_DIR") (pintype "bidirectional"))
      (node (ref "U5") (pin "42") (pinfunction "PC7_A15_IC3_CLK0_42") (pintype "bidirectional"))
    )
    (net (code "48") (name "/Z-STEP") (class "Default")
      (node (ref "P3") (pin "STEP") (pinfunction "STEP_STEP") (pintype "bidirectional"))
      (node (ref "U5") (pin "44") (pinfunction "PA7_AD7_44") (pintype "bidirectional"))
    )
    (net (code "49") (name "/Z-STOP") (class "Default")
      (node (ref "Q5") (pin "3") (pinfunction "C_3") (pintype "passive"))
      (node (ref "U5") (pin "1") (pinfunction "PE6_INT6_AIN0_1") (pintype "bidirectional"))
    )
    (net (code "50") (name "/~{E1-ENABLE}") (class "Default")
      (node (ref "P4") (pin "!EN") (pinfunction "~{ENABLE}_!EN") (pintype "input"))
      (node (ref "R22") (pin "2") (pinfunction "2_2") (pintype "passive"))
      (node (ref "U5") (pin "38") (pinfunction "PC3_A11_T3_38") (pintype "bidirectional"))
    )
    (net (code "51") (name "/~{E2-ENABLE}") (class "Default")
      (node (ref "U5") (pin "35") (pinfunction "PC0_A8_35") (pintype "bidirectional"))
    )
    (net (code "52") (name "/~{HOTBED}") (class "Default")
      (node (ref "R10") (pin "1") (pinfunction "1_1") (pintype "passive"))
      (node (ref "R11") (pin "1") (pinfunction "1_1") (pintype "passive"))
      (node (ref "U5") (pin "39") (pinfunction "PC4_A12_OC3C_39") (pintype "bidirectional"))
    )
    (net (code "53") (name "/~{HOTEND-1}") (class "Default")
      (node (ref "R8") (pin "1") (pinfunction "1_1") (pintype "passive"))
      (node (ref "R9") (pin "1") (pinfunction "1_1") (pintype "passive"))
      (node (ref "U5") (pin "40") (pinfunction "PC5_A13_OC3B_40") (pintype "bidirectional"))
    )
    (net (code "54") (name "/~{HOTEND-2}") (class "Default")
      (node (ref "U5") (pin "58") (pinfunction "PF3_ADC3_58") (pintype "bidirectional"))
    )
    (net (code "55") (name "/~{PWM-FAN}") (class "Default")
      (node (ref "R2") (pin "1") (pinfunction "1_1") (pintype "passive"))
      (node (ref "R3") (pin "1") (pinfunction "1_1") (pintype "passive"))
      (node (ref "U5") (pin "41") (pinfunction "PC6_A14_OC3A_41") (pintype "bidirectional"))
    )
    (net (code "56") (name "/~{RESET}") (class "Default")
      (node (ref "JP5") (pin "2") (pinfunction "2_2") (pintype "passive"))
      (node (ref "R12") (pin "1") (pinfunction "1_1") (pintype "passive"))
      (node (ref "S1") (pin "3") (pinfunction "3_3") (pintype "passive"))
      (node (ref "S1") (pin "4") (pinfunction "4_4") (pintype "passive"))
      (node (ref "U5") (pin "20") (pinfunction "/RESET_20") (pintype "bidirectional"))
    )
    (net (code "57") (name "/~{X-ENABLE}") (class "Default")
      (node (ref "P1") (pin "!EN") (pinfunction "~{ENABLE}_!EN") (pintype "input"))
      (node (ref "R20") (pin "2") (pinfunction "2_2") (pintype "passive"))
      (node (ref "U5") (pin "51") (pinfunction "PA0_AD0_51") (pintype "bidirectional"))
    )
    (net (code "58") (name "/~{Y-ENABLE}") (class "Default")
      (node (ref "P2") (pin "!EN") (pinfunction "~{ENABLE}_!EN") (pintype "input"))
      (node (ref "R19") (pin "2") (pinfunction "2_2") (pintype "passive"))
      (node (ref "U5") (pin "48") (pinfunction "PA3_AD3_48") (pintype "bidirectional"))
    )
    (net (code "59") (name "/~{Z-ENABLE}") (class "Default")
      (node (ref "P3") (pin "!EN") (pinfunction "~{ENABLE}_!EN") (pintype "input"))
      (node (ref "R21") (pin "2") (pinfunction "2_2") (pintype "passive"))
      (node (ref "U5") (pin "45") (pinfunction "PA6_AD6_45") (pintype "bidirectional"))
    )
    (net (code "60") (name "5V") (class "Default")
      (node (ref "C10") (pin "1") (pinfunction "1_1") (pintype "passive"))
      (node (ref "C3") (pin "1") (pinfunction "1_1") (pintype "passive"))
      (node (ref "C6") (pin "2") (pinfunction "2_2") (pintype "passive"))
      (node (ref "C7") (pin "2") (pinfunction "2_2") (pintype "passive"))
      (node (ref "C8") (pin "1") (pinfunction "1_1") (pintype "passive"))
      (node (ref "J8") (pin "2") (pinfunction "2_2") (pintype "passive"))
      (node (ref "JP4") (pin "3") (pinfunction "3_3") (pintype "passive"))
      (node (ref "JP5") (pin "5") (pinfunction "5_5") (pintype "passive"))
      (node (ref "JP6") (pin "3") (pinfunction "3_3") (pintype "passive"))
      (node (ref "L1") (pin "2") (pinfunction "2_2") (pintype "passive"))
      (node (ref "P1") (pin "VDD") (pinfunction "VDD_VDD") (pintype "power_in"))
      (node (ref "P2") (pin "VDD") (pinfunction "VDD_VDD") (pintype "power_in"))
      (node (ref "P3") (pin "VDD") (pinfunction "VDD_VDD") (pintype "power_in"))
      (node (ref "P4") (pin "VDD") (pinfunction "VDD_VDD") (pintype "power_in"))
      (node (ref "R1") (pin "2") (pinfunction "2_2") (pintype "passive"))
      (node (ref "R12") (pin "2") (pinfunction "2_2") (pintype "passive"))
      (node (ref "R13") (pin "2") (pinfunction "2_2") (pintype "passive"))
      (node (ref "R16") (pin "2") (pinfunction "2_2") (pintype "passive"))
      (node (ref "R17") (pin "2") (pinfunction "2_2") (pintype "passive"))
      (node (ref "R19") (pin "1") (pinfunction "1_1") (pintype "passive"))
      (node (ref "R20") (pin "1") (pinfunction "1_1") (pintype "passive"))
      (node (ref "R21") (pin "1") (pinfunction "1_1") (pintype "passive"))
      (node (ref "R22") (pin "1") (pinfunction "1_1") (pintype "passive"))
      (node (ref "R4") (pin "1") (pinfunction "1_1") (pintype "passive"))
      (node (ref "SJ1") (pin "2") (pinfunction "2_2") (pintype "passive"))
      (node (ref "SJ10") (pin "2") (pinfunction "2_2") (pintype "passive"))
      (node (ref "SJ12") (pin "2") (pinfunction "2_2") (pintype "passive"))
      (node (ref "SJ13") (pin "2") (pinfunction "2_2") (pintype "passive"))
      (node (ref "SJ14") (pin "2") (pinfunction "2_2") (pintype "passive"))
      (node (ref "SJ15") (pin "2") (pinfunction "2_2") (pintype "passive"))
      (node (ref "SJ2") (pin "2") (pinfunction "2_2") (pintype "passive"))
      (node (ref "SJ3") (pin "2") (pinfunction "2_2") (pintype "passive"))
      (node (ref "SJ4") (pin "2") (pinfunction "2_2") (pintype "passive"))
      (node (ref "SJ5") (pin "2") (pinfunction "2_2") (pintype "passive"))
      (node (ref "SJ7") (pin "2") (pinfunction "2_2") (pintype "passive"))
      (node (ref "SJ8") (pin "2") (pinfunction "2_2") (pintype "passive"))
      (node (ref "SJ9") (pin "2") (pinfunction "2_2") (pintype "passive"))
      (node (ref "U3") (pin "1") (pinfunction "IN_1") (pintype "power_in"))
      (node (ref "U4") (pin "14") (pinfunction "VCCB_14") (pintype "power_in"))
      (node (ref "U5") (pin "21") (pinfunction "VCC_21") (pintype "power_in"))
      (node (ref "U5") (pin "52") (pinfunction "VCC_52") (pintype "power_in"))
      (node (ref "U5") (pin "62") (pinfunction "AREF_62") (pintype "power_in"))
      (node (ref "U5") (pin "64") (pinfunction "AVCC_64") (pintype "power_in"))
    )
    (net (code "61") (name "12V") (class "Default")
      (node (ref "C1") (pin "1") (pinfunction "1_1") (pintype "passive"))
      (node (ref "C17") (pin "+") (pinfunction "+_+") (pintype "passive"))
      (node (ref "C18") (pin "+") (pinfunction "+_+") (pintype "passive"))
      (node (ref "C19") (pin "+") (pinfunction "+_+") (pintype "passive"))
      (node (ref "C2") (pin "+") (pinfunction "+_+") (pintype "passive"))
      (node (ref "C20") (pin "+") (pinfunction "+_+") (pintype "passive"))
      (node (ref "F2") (pin "P$3") (pinfunction "P$3_P$3") (pintype "passive"))
      (node (ref "F2") (pin "P$4") (pinfunction "P$4_P$4") (pintype "passive"))
      (node (ref "J1") (pin "1") (pinfunction "1_1") (pintype "passive"))
      (node (ref "J4") (pin "1") (pinfunction "1_1") (pintype "passive"))
      (node (ref "J7") (pin "3") (pinfunction "3_3") (pintype "power_in"))
      (node (ref "J7") (pin "4") (pinfunction "4_4") (pintype "power_in"))
      (node (ref "J8") (pin "3") (pinfunction "3_3") (pintype "passive"))
      (node (ref "J9") (pin "3") (pinfunction "3_3") (pintype "power_in"))
      (node (ref "J9") (pin "4") (pinfunction "4_4") (pintype "power_in"))
      (node (ref "JP4") (pin "1") (pinfunction "1_1") (pintype "passive"))
      (node (ref "JP6") (pin "1") (pinfunction "1_1") (pintype "passive"))
      (node (ref "P1") (pin "VMOT") (pinfunction "VMOT_VMOT") (pintype "power_in"))
      (node (ref "P2") (pin "VMOT") (pinfunction "VMOT_VMOT") (pintype "power_in"))
      (node (ref "P3") (pin "VMOT") (pinfunction "VMOT_VMOT") (pintype "power_in"))
      (node (ref "P4") (pin "VMOT") (pinfunction "VMOT_VMOT") (pintype "power_in"))
      (node (ref "U1") (pin "4") (pinfunction "~{SHDN}_4") (pintype "input"))
      (node (ref "U1") (pin "5") (pinfunction "VIN_5") (pintype "power_in"))
    )
    (net (code "62") (name "GND") (class "Default")
      (node (ref "C1") (pin "2") (pinfunction "2_2") (pintype "passive"))
      (node (ref "C10") (pin "2") (pinfunction "2_2") (pintype "passive"))
      (node (ref "C11") (pin "2") (pinfunction "2_2") (pintype "passive"))
      (node (ref "C12") (pin "1") (pinfunction "1_1") (pintype "passive"))
      (node (ref "C13") (pin "1") (pinfunction "1_1") (pintype "passive"))
      (node (ref "C14") (pin "1") (pinfunction "1_1") (pintype "passive"))
      (node (ref "C15") (pin "1") (pinfunction "1_1") (pintype "passive"))
      (node (ref "C17") (pin "-") (pinfunction "-_-") (pintype "passive"))
      (node (ref "C18") (pin "-") (pinfunction "-_-") (pintype "passive"))
      (node (ref "C19") (pin "-") (pinfunction "-_-") (pintype "passive"))
      (node (ref "C2") (pin "-") (pinfunction "-_-") (pintype "passive"))
      (node (ref "C20") (pin "-") (pinfunction "-_-") (pintype "passive"))
      (node (ref "C3") (pin "2") (pinfunction "2_2") (pintype "passive"))
      (node (ref "C5") (pin "1") (pinfunction "1_1") (pintype "passive"))
      (node (ref "C6") (pin "1") (pinfunction "1_1") (pintype "passive"))
      (node (ref "C7") (pin "1") (pinfunction "1_1") (pintype "passive"))
      (node (ref "C8") (pin "2") (pinfunction "2_2") (pintype "passive"))
      (node (ref "C9") (pin "1") (pinfunction "1_1") (pintype "passive"))
      (node (ref "D1") (pin "A") (pinfunction "A_A") (pintype "passive"))
      (node (ref "D2") (pin "A") (pinfunction "A_A") (pintype "passive"))
      (node (ref "J1") (pin "2") (pinfunction "2_2") (pintype "passive"))
      (node (ref "J11") (pin "2") (pinfunction "2_2") (pintype "passive"))
      (node (ref "J12") (pin "2") (pinfunction "2_2") (pintype "passive"))
      (node (ref "J2") (pin "6") (pinfunction "GND_6") (pintype "power_in"))
      (node (ref "J2") (pin "C1") (pinfunction "SHEILD_C1") (pintype "bidirectional"))
      (node (ref "J2") (pin "C2") (pinfunction "SHIELD_C2") (pintype "bidirectional"))
      (node (ref "J2") (pin "C3") (pinfunction "SHIELD_C3") (pintype "bidirectional"))
      (node (ref "J2") (pin "C4") (pinfunction "SHIELD_C4") (pintype "bidirectional"))
      (node (ref "J2") (pin "CD1") (pinfunction "CD1_CD1") (pintype "bidirectional"))
      (node (ref "J3") (pin "GND") (pinfunction "GND_GND") (pintype "bidirectional"))
      (node (ref "J3") (pin "GND1") (pinfunction "GND_GND1") (pintype "bidirectional"))
      (node (ref "J3") (pin "GND2") (pinfunction "GND_GND2") (pintype "bidirectional"))
      (node (ref "J3") (pin "GND3") (pinfunction "GND_GND3") (pintype "bidirectional"))
      (node (ref "J3") (pin "GND4") (pinfunction "GND_GND4") (pintype "bidirectional"))
      (node (ref "J3") (pin "GND5") (pinfunction "GND_GND5") (pintype "bidirectional"))
      (node (ref "J3") (pin "GND6") (pinfunction "GND_GND6") (pintype "bidirectional"))
      (node (ref "J3") (pin "GND7") (pinfunction "GND_GND7") (pintype "bidirectional"))
      (node (ref "J3") (pin "GND8") (pinfunction "GND_GND8") (pintype "bidirectional"))
      (node (ref "J5") (pin "3") (pinfunction "3_3") (pintype "power_in"))
      (node (ref "J5") (pin "4") (pinfunction "4_4") (pintype "power_in"))
      (node (ref "J6") (pin "4") (pinfunction "S_4") (pintype "passive"))
      (node (ref "J6") (pin "5") (pinfunction "S_5") (pintype "passive"))
      (node (ref "J6") (pin "6") (pinfunction "S_6") (pintype "passive"))
      (node (ref "J8") (pin "1") (pinfunction "1_1") (pintype "passive"))
      (node (ref "JP10") (pin "3") (pinfunction "3_3") (pintype "passive"))
      (node (ref "JP3") (pin "2") (pinfunction "2_2") (pintype "passive"))
      (node (ref "JP5") (pin "1") (pinfunction "1_1") (pintype "passive"))
      (node (ref "JP7") (pin "3") (pinfunction "3_3") (pintype "passive"))
      (node (ref "JP8") (pin "3") (pinfunction "3_3") (pintype "passive"))
      (node (ref "JP9") (pin "3") (pinfunction "3_3") (pintype "passive"))
      (node (ref "LED1") (pin "C") (pinfunction "C_C") (pintype "passive"))
      (node (ref "P1") (pin "GNDMOT") (pinfunction "GNDMOT_GNDMOT") (pintype "power_in"))
      (node (ref "P1") (pin "GNDVDD") (pinfunction "GNDVDD_GNDVDD") (pintype "power_in"))
      (node (ref "P2") (pin "GNDMOT") (pinfunction "GNDMOT_GNDMOT") (pintype "power_in"))
      (node (ref "P2") (pin "GNDVDD") (pinfunction "GNDVDD_GNDVDD") (pintype "power_in"))
      (node (ref "P3") (pin "GNDMOT") (pinfunction "GNDMOT_GNDMOT") (pintype "power_in"))
      (node (ref "P3") (pin "GNDVDD") (pinfunction "GNDVDD_GNDVDD") (pintype "power_in"))
      (node (ref "P4") (pin "GNDMOT") (pinfunction "GNDMOT_GNDMOT") (pintype "power_in"))
      (node (ref "P4") (pin "GNDVDD") (pinfunction "GNDVDD_GNDVDD") (pintype "power_in"))
      (node (ref "Q1") (pin "2") (pinfunction "S_2") (pintype "passive"))
      (node (ref "Q2") (pin "1") (pinfunction "S1_1") (pintype "passive"))
      (node (ref "Q2") (pin "2") (pinfunction "S2_2") (pintype "passive"))
      (node (ref "Q2") (pin "3") (pinfunction "S3_3") (pintype "passive"))
      (node (ref "Q3") (pin "1") (pinfunction "S1_1") (pintype "passive"))
      (node (ref "Q3") (pin "2") (pinfunction "S2_2") (pintype "passive"))
      (node (ref "Q3") (pin "3") (pinfunction "S3_3") (pintype "passive"))
      (node (ref "Q5") (pin "2") (pinfunction "E_2") (pintype "passive"))
      (node (ref "R10") (pin "2") (pinfunction "2_2") (pintype "passive"))
      (node (ref "R2") (pin "2") (pinfunction "2_2") (pintype "passive"))
      (node (ref "R5") (pin "2") (pinfunction "2_2") (pintype "passive"))
      (node (ref "R8") (pin "2") (pinfunction "2_2") (pintype "passive"))
      (node (ref "S1") (pin "1") (pinfunction "1_1") (pintype "passive"))
      (node (ref "S1") (pin "2") (pinfunction "2_2") (pintype "passive"))
      (node (ref "SCREW1") (pin "GND") (pinfunction "P$1_GND") (pintype "bidirectional"))
      (node (ref "SCREW2") (pin "GND") (pinfunction "P$1_GND") (pintype "bidirectional"))
      (node (ref "SCREW3") (pin "GND") (pinfunction "P$1_GND") (pintype "bidirectional"))
      (node (ref "SCREW4") (pin "GND") (pinfunction "P$1_GND") (pintype "bidirectional"))
      (node (ref "U1") (pin "2") (pinfunction "GND_2") (pintype "power_in"))
      (node (ref "U2") (pin "2") (pinfunction "GND_2") (pintype "power_in"))
      (node (ref "U3") (pin "3") (pinfunction "GND_3") (pintype "power_in"))
      (node (ref "U4") (pin "7") (pinfunction "GND_7") (pintype "power_in"))
      (node (ref "U5") (pin "22") (pinfunction "GND_22") (pintype "power_in"))
      (node (ref "U5") (pin "53") (pinfunction "GND_53") (pintype "power_in"))
      (node (ref "U5") (pin "6") (pinfunction "UGND_6") (pintype "power_in"))
      (node (ref "U5") (pin "63") (pinfunction "AGND_63") (pintype "power_in"))
    )
    (net (code "63") (name "Net-(F1-PadP$2)") (class "Default")
      (node (ref "F1") (pin "P$2") (pinfunction "P$2_P$2") (pintype "passive"))
      (node (ref "J4") (pin "2") (pinfunction "2_2") (pintype "passive"))
    )
    (net (code "64") (name "Net-(J6A-S)") (class "Default")
      (node (ref "F2") (pin "P$1") (pinfunction "P$1_P$1") (pintype "passive"))
      (node (ref "F2") (pin "P$2") (pinfunction "P$2_P$2") (pintype "passive"))
      (node (ref "J5") (pin "1") (pinfunction "1_1") (pintype "power_in"))
      (node (ref "J5") (pin "2") (pinfunction "2_2") (pintype "power_in"))
      (node (ref "J6") (pin "1") (pinfunction "S_1") (pintype "passive"))
      (node (ref "J6") (pin "2") (pinfunction "S_2") (pintype "passive"))
      (node (ref "J6") (pin "3") (pinfunction "S_3") (pintype "passive"))
    )
    (net (code "65") (name "Net-(JP6-Pad2)") (class "Default")
      (node (ref "JP6") (pin "2") (pinfunction "2_2") (pintype "passive"))
      (node (ref "JP7") (pin "2") (pinfunction "2_2") (pintype "passive"))
    )
    (net (code "66") (name "Net-(JP10-Pad2)") (class "Default")
      (node (ref "JP10") (pin "2") (pinfunction "2_2") (pintype "passive"))
      (node (ref "JP4") (pin "2") (pinfunction "2_2") (pintype "passive"))
      (node (ref "JP8") (pin "2") (pinfunction "2_2") (pintype "passive"))
      (node (ref "JP9") (pin "2") (pinfunction "2_2") (pintype "passive"))
    )
    (net (code "67") (name "Net-(LED1-PadA)") (class "Default")
      (node (ref "LED1") (pin "A") (pinfunction "A_A") (pintype "passive"))
      (node (ref "R1") (pin "1") (pinfunction "1_1") (pintype "passive"))
    )
    (net (code "68") (name "Net-(P1-MOT-1A)") (class "Default")
      (node (ref "JP11") (pin "3") (pinfunction "3_3") (pintype "passive"))
      (node (ref "P1") (pin "1A") (pinfunction "MOT-1A_1A") (pintype "power_in"))
    )
    (net (code "69") (name "Net-(P1-MOT-1B)") (class "Default")
      (node (ref "JP11") (pin "4") (pinfunction "4_4") (pintype "passive"))
      (node (ref "P1") (pin "1B") (pinfunction "MOT-1B_1B") (pintype "power_in"))
    )
    (net (code "70") (name "Net-(P1-MOT-2A)") (class "Default")
      (node (ref "JP11") (pin "2") (pinfunction "2_2") (pintype "passive"))
      (node (ref "P1") (pin "2A") (pinfunction "MOT-2A_2A") (pintype "power_in"))
    )
    (net (code "71") (name "Net-(P1-MOT-2B)") (class "Default")
      (node (ref "JP11") (pin "1") (pinfunction "1_1") (pintype "passive"))
      (node (ref "P1") (pin "2B") (pinfunction "MOT-2B_2B") (pintype "power_in"))
    )
    (net (code "72") (name "Net-(P1-PadMS1)") (class "Default")
      (node (ref "P1") (pin "MS1") (pinfunction "MS1_MS1") (pintype "input"))
      (node (ref "SJ12") (pin "1") (pinfunction "1_1") (pintype "passive"))
    )
    (net (code "73") (name "Net-(P1-PadMS2)") (class "Default")
      (node (ref "P1") (pin "MS2") (pinfunction "MS2_MS2") (pintype "input"))
      (node (ref "SJ7") (pin "1") (pinfunction "1_1") (pintype "passive"))
    )
    (net (code "74") (name "Net-(P1-PadMS3)") (class "Default")
      (node (ref "P1") (pin "MS3") (pinfunction "MS3_MS3") (pintype "input"))
      (node (ref "SJ2") (pin "1") (pinfunction "1_1") (pintype "passive"))
    )
    (net (code "75") (name "Net-(P1-~{RESET})") (class "Default")
      (node (ref "P1") (pin "!RST") (pinfunction "~{RESET}_!RST") (pintype "input"))
      (node (ref "P1") (pin "!SLP") (pinfunction "~{SLEEP}_!SLP") (pintype "input"))
    )
    (net (code "76") (name "Net-(P2-MOT-1A)") (class "Default")
      (node (ref "JP12") (pin "3") (pinfunction "3_3") (pintype "passive"))
      (node (ref "P2") (pin "1A") (pinfunction "MOT-1A_1A") (pintype "power_in"))
    )
    (net (code "77") (name "Net-(P2-MOT-1B)") (class "Default")
      (node (ref "JP12") (pin "4") (pinfunction "4_4") (pintype "passive"))
      (node (ref "P2") (pin "1B") (pinfunction "MOT-1B_1B") (pintype "power_in"))
    )
    (net (code "78") (name "Net-(P2-MOT-2A)") (class "Default")
      (node (ref "JP12") (pin "2") (pinfunction "2_2") (pintype "passive"))
      (node (ref "P2") (pin "2A") (pinfunction "MOT-2A_2A") (pintype "power_in"))
    )
    (net (code "79") (name "Net-(P2-MOT-2B)") (class "Default")
      (node (ref "JP12") (pin "1") (pinfunction "1_1") (pintype "passive"))
      (node (ref "P2") (pin "2B") (pinfunction "MOT-2B_2B") (pintype "power_in"))
    )
    (net (code "80") (name "Net-(P2-PadMS1)") (class "Default")
      (node (ref "P2") (pin "MS1") (pinfunction "MS1_MS1") (pintype "input"))
      (node (ref "SJ13") (pin "1") (pinfunction "1_1") (pintype "passive"))
    )
    (net (code "81") (name "Net-(P2-PadMS2)") (class "Default")
      (node (ref "P2") (pin "MS2") (pinfunction "MS2_MS2") (pintype "input"))
      (node (ref "SJ8") (pin "1") (pinfunction "1_1") (pintype "passive"))
    )
    (net (code "82") (name "Net-(P2-PadMS3)") (class "Default")
      (node (ref "P2") (pin "MS3") (pinfunction "MS3_MS3") (pintype "input"))
      (node (ref "SJ3") (pin "1") (pinfunction "1_1") (pintype "passive"))
    )
    (net (code "83") (name "Net-(P2-~{RESET})") (class "Default")
      (node (ref "P2") (pin "!RST") (pinfunction "~{RESET}_!RST") (pintype "input"))
      (node (ref "P2") (pin "!SLP") (pinfunction "~{SLEEP}_!SLP") (pintype "input"))
    )
    (net (code "84") (name "Net-(P3-MOT-1A)") (class "Default")
      (node (ref "JP15") (pin "3") (pinfunction "3_3") (pintype "passive"))
      (node (ref "P3") (pin "1A") (pinfunction "MOT-1A_1A") (pintype "power_in"))
    )
    (net (code "85") (name "Net-(P3-MOT-1B)") (class "Default")
      (node (ref "JP15") (pin "4") (pinfunction "4_4") (pintype "passive"))
      (node (ref "P3") (pin "1B") (pinfunction "MOT-1B_1B") (pintype "power_in"))
    )
    (net (code "86") (name "Net-(P3-MOT-2A)") (class "Default")
      (node (ref "JP15") (pin "2") (pinfunction "2_2") (pintype "passive"))
      (node (ref "P3") (pin "2A") (pinfunction "MOT-2A_2A") (pintype "power_in"))
    )
    (net (code "87") (name "Net-(P3-MOT-2B)") (class "Default")
      (node (ref "JP15") (pin "1") (pinfunction "1_1") (pintype "passive"))
      (node (ref "P3") (pin "2B") (pinfunction "MOT-2B_2B") (pintype "power_in"))
    )
    (net (code "88") (name "Net-(P3-PadMS1)") (class "Default")
      (node (ref "P3") (pin "MS1") (pinfunction "MS1_MS1") (pintype "input"))
      (node (ref "SJ14") (pin "1") (pinfunction "1_1") (pintype "passive"))
    )
    (net (code "89") (name "Net-(P3-PadMS2)") (class "Default")
      (node (ref "P3") (pin "MS2") (pinfunction "MS2_MS2") (pintype "input"))
      (node (ref "SJ9") (pin "1") (pinfunction "1_1") (pintype "passive"))
    )
    (net (code "90") (name "Net-(P3-PadMS3)") (class "Default")
      (node (ref "P3") (pin "MS3") (pinfunction "MS3_MS3") (pintype "input"))
      (node (ref "SJ4") (pin "1") (pinfunction "1_1") (pintype "passive"))
    )
    (net (code "91") (name "Net-(P3-~{RESET})") (class "Default")
      (node (ref "P3") (pin "!RST") (pinfunction "~{RESET}_!RST") (pintype "input"))
      (node (ref "P3") (pin "!SLP") (pinfunction "~{SLEEP}_!SLP") (pintype "input"))
    )
    (net (code "92") (name "Net-(P4-MOT-1A)") (class "Default")
      (node (ref "JP13") (pin "3") (pinfunction "3_3") (pintype "passive"))
      (node (ref "P4") (pin "1A") (pinfunction "MOT-1A_1A") (pintype "power_in"))
    )
    (net (code "93") (name "Net-(P4-MOT-1B)") (class "Default")
      (node (ref "JP13") (pin "4") (pinfunction "4_4") (pintype "passive"))
      (node (ref "P4") (pin "1B") (pinfunction "MOT-1B_1B") (pintype "power_in"))
    )
    (net (code "94") (name "Net-(P4-MOT-2A)") (class "Default")
      (node (ref "JP13") (pin "2") (pinfunction "2_2") (pintype "passive"))
      (node (ref "P4") (pin "2A") (pinfunction "MOT-2A_2A") (pintype "power_in"))
    )
    (net (code "95") (name "Net-(P4-MOT-2B)") (class "Default")
      (node (ref "JP13") (pin "1") (pinfunction "1_1") (pintype "passive"))
      (node (ref "P4") (pin "2B") (pinfunction "MOT-2B_2B") (pintype "power_in"))
    )
    (net (code "96") (name "Net-(P4-PadMS1)") (class "Default")
      (node (ref "P4") (pin "MS1") (pinfunction "MS1_MS1") (pintype "input"))
      (node (ref "SJ15") (pin "1") (pinfunction "1_1") (pintype "passive"))
    )
    (net (code "97") (name "Net-(P4-PadMS2)") (class "Default")
      (node (ref "P4") (pin "MS2") (pinfunction "MS2_MS2") (pintype "input"))
      (node (ref "SJ10") (pin "1") (pinfunction "1_1") (pintype "passive"))
    )
    (net (code "98") (name "Net-(P4-PadMS3)") (class "Default")
      (node (ref "P4") (pin "MS3") (pinfunction "MS3_MS3") (pintype "input"))
      (node (ref "SJ5") (pin "1") (pinfunction "1_1") (pintype "passive"))
    )
    (net (code "99") (name "Net-(P4-~{RESET})") (class "Default")
      (node (ref "P4") (pin "!RST") (pinfunction "~{RESET}_!RST") (pintype "input"))
      (node (ref "P4") (pin "!SLP") (pinfunction "~{SLEEP}_!SLP") (pintype "input"))
    )
    (net (code "100") (name "Net-(Q1-D)") (class "Default")
      (node (ref "D2") (pin "C") (pinfunction "C_C") (pintype "passive"))
      (node (ref "F1") (pin "P$1") (pinfunction "P$1_P$1") (pintype "passive"))
      (node (ref "Q1") (pin "3") (pinfunction "D_3") (pintype "passive"))
    )
    (net (code "101") (name "Net-(Q1-G)") (class "Default")
      (node (ref "Q1") (pin "1") (pinfunction "G_1") (pintype "passive"))
      (node (ref "R3") (pin "2") (pinfunction "2_2") (pintype "passive"))
    )
    (net (code "102") (name "Net-(Q2-D)") (class "Default")
      (node (ref "J7") (pin "1") (pinfunction "1_1") (pintype "power_in"))
      (node (ref "J7") (pin "2") (pinfunction "2_2") (pintype "power_in"))
      (node (ref "Q2") (pin "5-8") (pinfunction "D_5-8") (pintype "passive"))
    )
    (net (code "103") (name "Net-(Q2-G)") (class "Default")
      (node (ref "Q2") (pin "4") (pinfunction "G_4") (pintype "passive"))
      (node (ref "R9") (pin "2") (pinfunction "2_2") (pintype "passive"))
    )
    (net (code "104") (name "Net-(Q3-D)") (class "Default")
      (node (ref "J9") (pin "1") (pinfunction "1_1") (pintype "power_in"))
      (node (ref "J9") (pin "2") (pinfunction "2_2") (pintype "power_in"))
      (node (ref "Q3") (pin "5-8") (pinfunction "D_5-8") (pintype "passive"))
    )
    (net (code "105") (name "Net-(Q3-G)") (class "Default")
      (node (ref "Q3") (pin "4") (pinfunction "G_4") (pintype "passive"))
      (node (ref "R11") (pin "2") (pinfunction "2_2") (pintype "passive"))
    )
    (net (code "106") (name "Net-(Q5-B)") (class "Default")
      (node (ref "JP7") (pin "1") (pinfunction "1_1") (pintype "passive"))
      (node (ref "Q5") (pin "1") (pinfunction "B_1") (pintype "passive"))
    )
    (net (code "107") (name "Net-(U1-CB)") (class "Default")
      (node (ref "C4") (pin "2") (pinfunction "2_2") (pintype "passive"))
      (node (ref "U1") (pin "1") (pinfunction "CB_1") (pintype "passive"))
    )
    (net (code "108") (name "Net-(U1-FB)") (class "Default")
      (node (ref "R4") (pin "2") (pinfunction "2_2") (pintype "passive"))
      (node (ref "R5") (pin "1") (pinfunction "1_1") (pintype "passive"))
      (node (ref "U1") (pin "3") (pinfunction "FB_3") (pintype "passive"))
    )
    (net (code "109") (name "Net-(U1-SW)") (class "Default")
      (node (ref "C4") (pin "1") (pinfunction "1_1") (pintype "passive"))
      (node (ref "D1") (pin "C") (pinfunction "C_C") (pintype "passive"))
      (node (ref "L1") (pin "1") (pinfunction "1_1") (pintype "passive"))
      (node (ref "U1") (pin "6") (pinfunction "SW_6") (pintype "passive"))
    )
    (net (code "110") (name "Net-(U5-D+)") (class "Default")
      (node (ref "R7") (pin "2") (pinfunction "2_2") (pintype "passive"))
      (node (ref "U5") (pin "5") (pinfunction "D+_5") (pintype "bidirectional"))
    )
    (net (code "111") (name "Net-(U5-D-)") (class "Default")
      (node (ref "R6") (pin "2") (pinfunction "2_2") (pintype "passive"))
      (node (ref "U5") (pin "4") (pinfunction "D-_4") (pintype "bidirectional"))
    )
    (net (code "112") (name "Net-(U5-UCAP)") (class "Default")
      (node (ref "C9") (pin "2") (pinfunction "2_2") (pintype "passive"))
      (node (ref "U5") (pin "7") (pinfunction "UCAP_7") (pintype "power_in"))
    )
    (net (code "113") (name "unconnected-(J2-DAT1-Pad8)") (class "Default")
      (node (ref "J2") (pin "8") (pinfunction "DAT1_8") (pintype "bidirectional"))
    )
    (net (code "114") (name "unconnected-(J2-DAT2-Pad1)") (class "Default")
      (node (ref "J2") (pin "1") (pinfunction "DAT2_1") (pintype "bidirectional"))
    )
    (net (code "115") (name "unconnected-(U2-IO3-Pad4)") (class "Default")
      (node (ref "U2") (pin "4") (pinfunction "IO3_4") (pintype "bidirectional"))
    )
    (net (code "116") (name "unconnected-(U2-IO4-Pad6)") (class "Default")
      (node (ref "U2") (pin "6") (pinfunction "IO4_6") (pintype "bidirectional"))
    )
  )
)
